# PCB-DISPLAYDOGM2.net
KiCad netlist of a schematic drawn in EAGLE
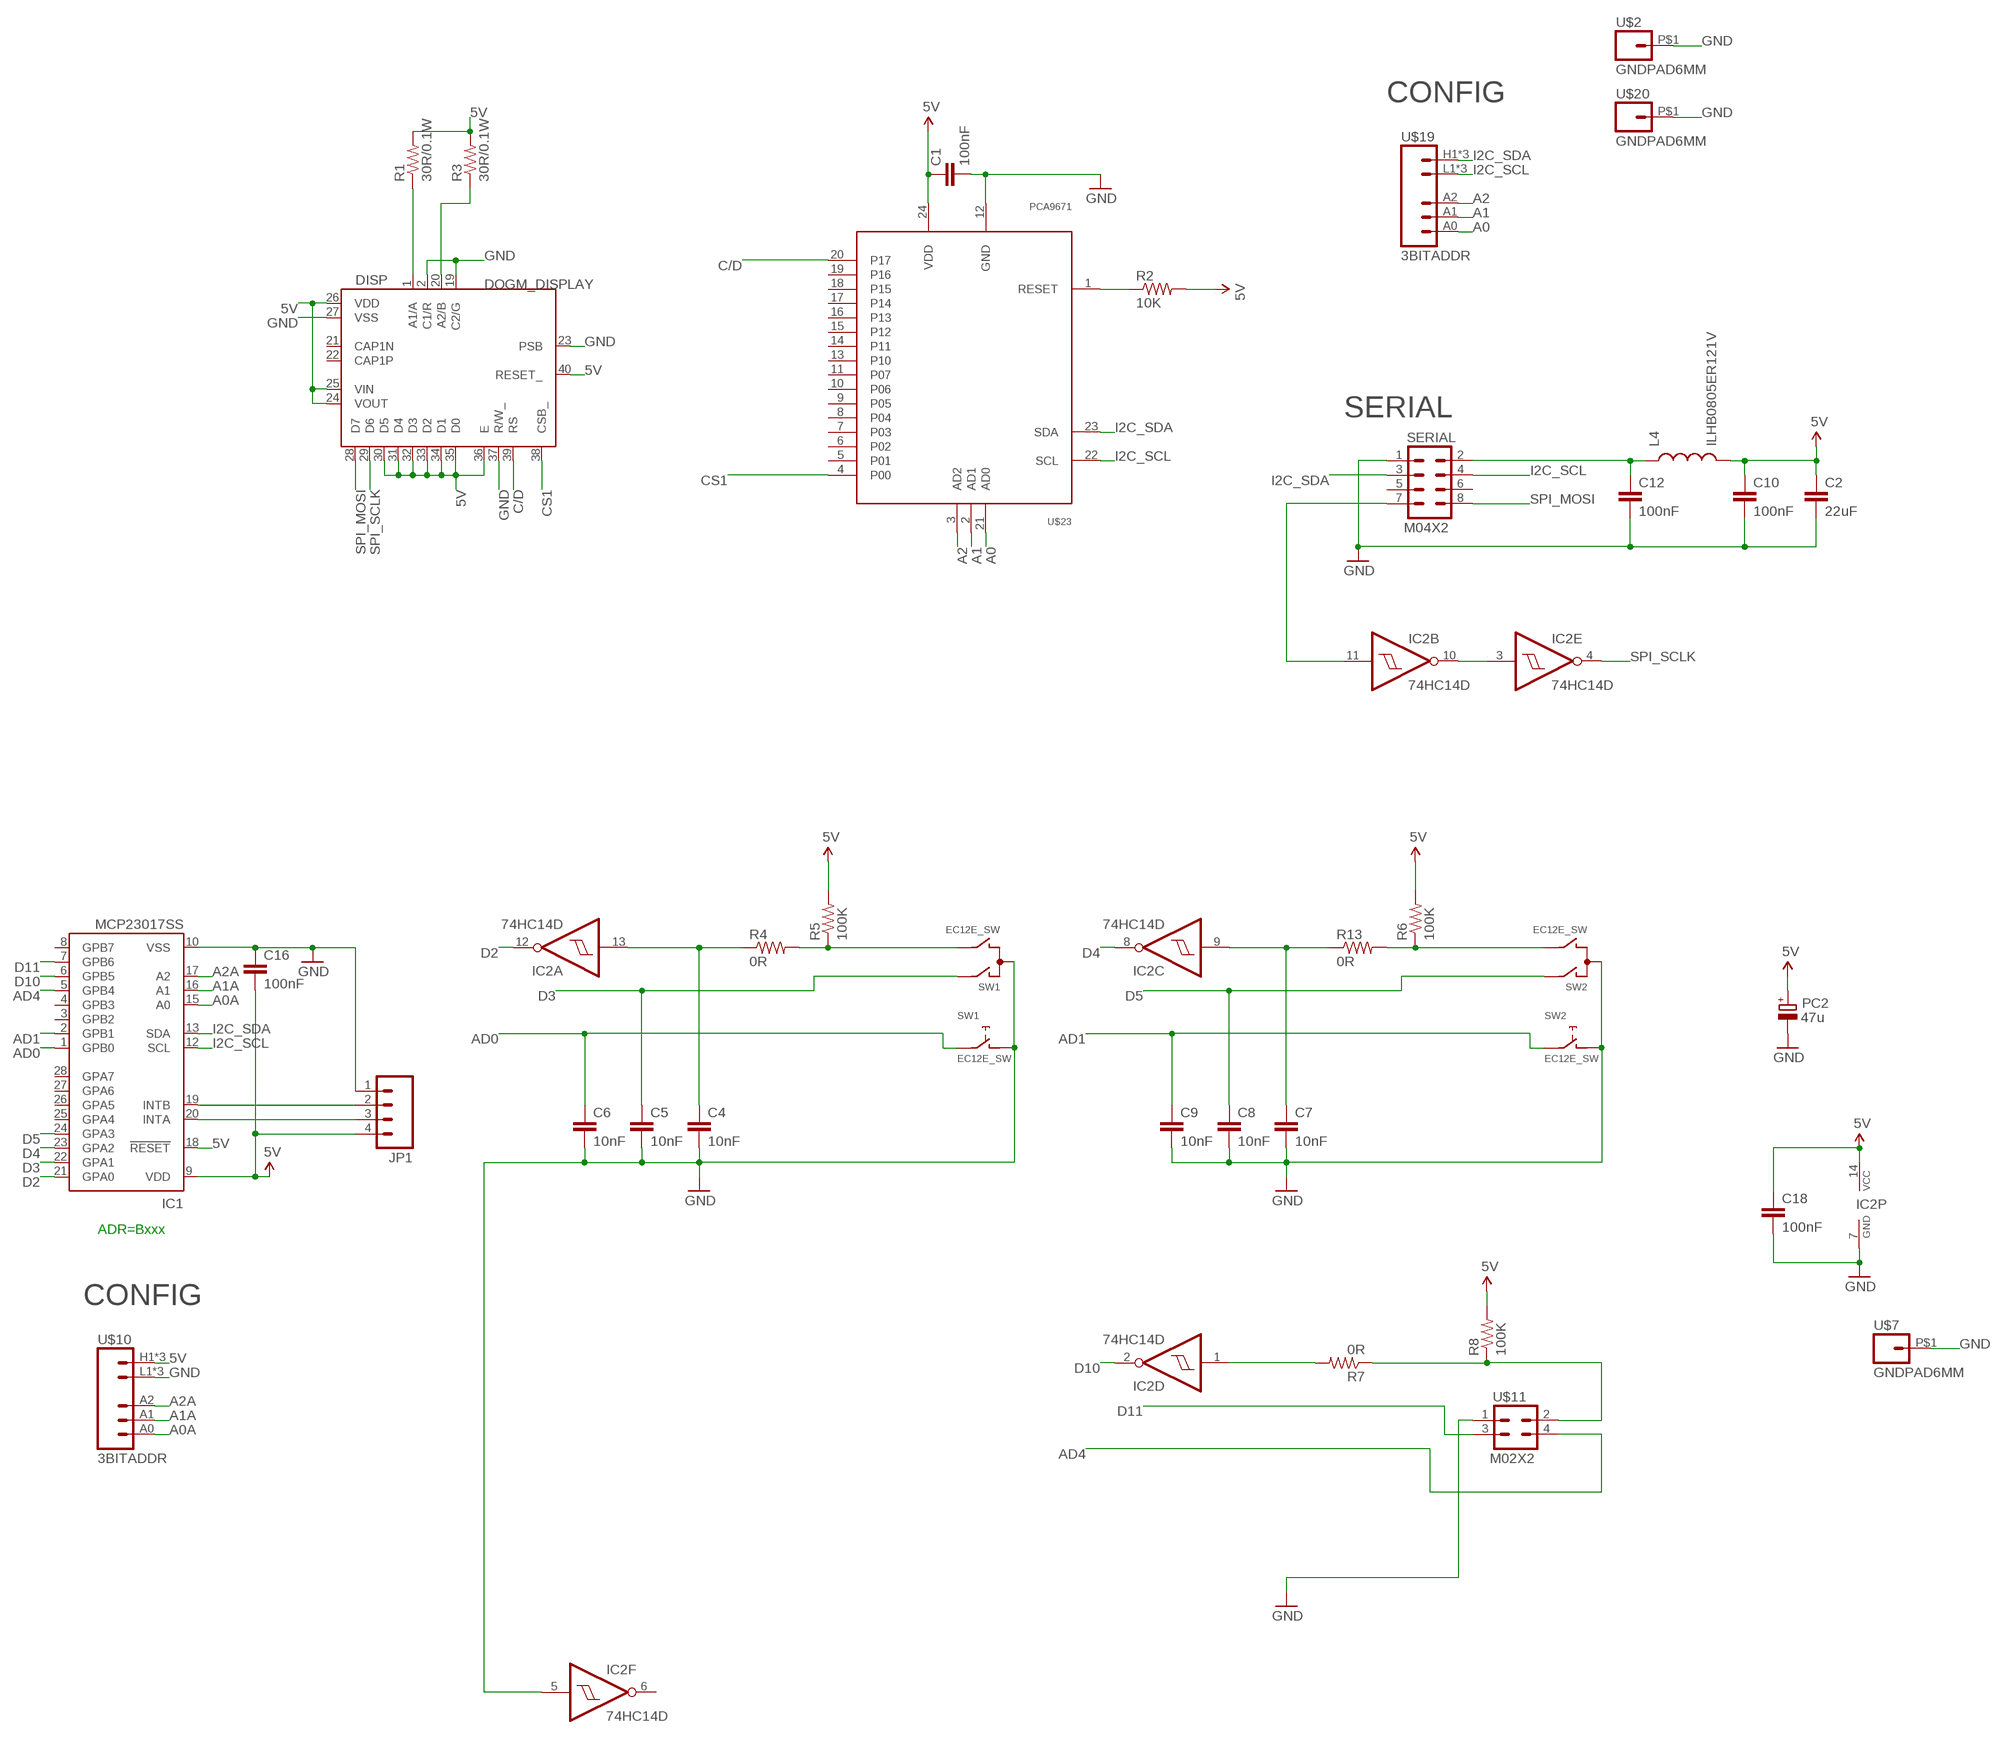
[diagram p0: schematic, sheet 1]

(export (version "E")
  (design (tool "Eeschema 10.0.6"))
  (components
    (comp (ref "C1")
      (value "100nF")
      (footprint "eagle-import:0603-CAP")
      (libsource (lib "eagle-import") (part "CAP0603-CAP"))
    )
    (comp (ref "C2")
      (value "22uF")
      (footprint "eagle-import:0805")
      (libsource (lib "eagle-import") (part "CAP0805"))
    )
    (comp (ref "C4")
      (value "10nF")
      (footprint "eagle-import:0603-CAP")
      (libsource (lib "eagle-import") (part "CAP0603-CAP"))
    )
    (comp (ref "C5")
      (value "10nF")
      (footprint "eagle-import:0603-CAP")
      (libsource (lib "eagle-import") (part "CAP0603-CAP"))
    )
    (comp (ref "C6")
      (value "10nF")
      (footprint "eagle-import:0603-CAP")
      (libsource (lib "eagle-import") (part "CAP0603-CAP"))
    )
    (comp (ref "C7")
      (value "10nF")
      (footprint "eagle-import:0603-CAP")
      (libsource (lib "eagle-import") (part "CAP0603-CAP"))
    )
    (comp (ref "C8")
      (value "10nF")
      (footprint "eagle-import:0603-CAP")
      (libsource (lib "eagle-import") (part "CAP0603-CAP"))
    )
    (comp (ref "C9")
      (value "10nF")
      (footprint "eagle-import:0603-CAP")
      (libsource (lib "eagle-import") (part "CAP0603-CAP"))
    )
    (comp (ref "C10")
      (value "100nF")
      (footprint "eagle-import:0603-CAP")
      (libsource (lib "eagle-import") (part "CAP0603-CAP"))
    )
    (comp (ref "C12")
      (value "100nF")
      (footprint "eagle-import:0603-CAP")
      (libsource (lib "eagle-import") (part "CAP0603-CAP"))
    )
    (comp (ref "C16")
      (value "100nF")
      (footprint "eagle-import:0603-CAP")
      (libsource (lib "eagle-import") (part "CAP0603-CAP"))
    )
    (comp (ref "C18")
      (value "100nF")
      (footprint "eagle-import:0603-CAP")
      (libsource (lib "eagle-import") (part "CAP0603-CAP"))
    )
    (comp (ref "DISP")
      (value "DOGM_DISPLAY")
      (footprint "eagle-import:DOGM")
      (libsource (lib "eagle-import") (part "DOGM_DISPLAY"))
    )
    (comp (ref "IC1")
      (value "MCP23017SS")
      (footprint "eagle-import:SSOP28")
      (fields
        (field (name "MF") "MICROCHIP")
        (field (name "MPN") "MCP23017-E/SS")
        (field (name "MPN_1") "MCP23017-E/SS")
        (field (name "OC_FARNELL") "1467674")
        (field (name "OC_NEWARK") "31K2960")
      )
      (libsource (lib "eagle-import") (part "MCP23017SS"))
    )
    (comp (ref "IC2")
      (value "74HC14D")
      (footprint "eagle-import:SO14")
      (libsource (lib "eagle-import") (part "7414DHC"))
    )
    (comp (ref "JP1")
      (value "M04PTH")
      (footprint "eagle-import:1X04")
      (libsource (lib "eagle-import") (part "M04PTH"))
    )
    (comp (ref "L4")
      (value "ILHB0805ER121V")
      (footprint "eagle-import:0805")
      (libsource (lib "eagle-import") (part "INDUCTOR0805"))
    )
    (comp (ref "PC2")
      (value "47u")
      (footprint "eagle-import:PANASONIC_D")
      (libsource (lib "eagle-import") (part "CPOL-EUD"))
    )
    (comp (ref "R1")
      (value "30R/0.1W")
      (footprint "eagle-import:0603-RES")
      (libsource (lib "eagle-import") (part "RESISTOR0603-RES"))
    )
    (comp (ref "R2")
      (value "10K")
      (footprint "eagle-import:0603-RES")
      (libsource (lib "eagle-import") (part "RESISTOR0603-RES"))
    )
    (comp (ref "R3")
      (value "30R/0.1W")
      (footprint "eagle-import:0603-RES")
      (libsource (lib "eagle-import") (part "RESISTOR0603-RES"))
    )
    (comp (ref "R4")
      (value "0R")
      (footprint "eagle-import:0603-RES")
      (libsource (lib "eagle-import") (part "RESISTOR0603-RES"))
    )
    (comp (ref "R5")
      (value "100K")
      (footprint "eagle-import:0603-RES")
      (libsource (lib "eagle-import") (part "RESISTOR0603-RES"))
    )
    (comp (ref "R6")
      (value "100K")
      (footprint "eagle-import:0603-RES")
      (libsource (lib "eagle-import") (part "RESISTOR0603-RES"))
    )
    (comp (ref "R7")
      (value "0R")
      (footprint "eagle-import:0603-RES")
      (libsource (lib "eagle-import") (part "RESISTOR0603-RES"))
    )
    (comp (ref "R8")
      (value "100K")
      (footprint "eagle-import:0603-RES")
      (libsource (lib "eagle-import") (part "RESISTOR0603-RES"))
    )
    (comp (ref "R13")
      (value "0R")
      (footprint "eagle-import:0603-RES")
      (libsource (lib "eagle-import") (part "RESISTOR0603-RES"))
    )
    (comp (ref "SERIAL")
      (value "M04X2")
      (footprint "eagle-import:2X4")
      (libsource (lib "eagle-import") (part "M04X2"))
    )
    (comp (ref "SW1")
      (value "EC12E_SW")
      (footprint "eagle-import:ALPS_EC12E_SW")
      (fields (field (name "MPN") "EC12E2424407"))
      (libsource (lib "eagle-import") (part "EC12E_SW"))
    )
    (comp (ref "SW2")
      (value "EC12E_SW")
      (footprint "eagle-import:ALPS_EC12E_SW")
      (fields (field (name "MPN") "EC12E2424407"))
      (libsource (lib "eagle-import") (part "EC12E_SW"))
    )
    (comp (ref "U$2")
      (value "GNDPAD6MM")
      (footprint "eagle-import:3.2MMPAD6MM")
      (libsource (lib "eagle-import") (part "GNDPAD6MM"))
    )
    (comp (ref "U$7")
      (value "GNDPAD6MM")
      (footprint "eagle-import:3.2MMPAD6MM")
      (libsource (lib "eagle-import") (part "GNDPAD6MM"))
    )
    (comp (ref "U$10")
      (value "3BITADDR")
      (footprint "eagle-import:3BITADDR")
      (libsource (lib "eagle-import") (part "3BITADDR"))
    )
    (comp (ref "U$11")
      (value "M02X2")
      (footprint "eagle-import:2X2")
      (libsource (lib "eagle-import") (part "M02X2"))
    )
    (comp (ref "U$19")
      (value "3BITADDR")
      (footprint "eagle-import:3BITADDR")
      (libsource (lib "eagle-import") (part "3BITADDR"))
    )
    (comp (ref "U$20")
      (value "GNDPAD6MM")
      (footprint "eagle-import:3.2MMPAD6MM")
      (libsource (lib "eagle-import") (part "GNDPAD6MM"))
    )
    (comp (ref "U$23")
      (value "PCA9671")
      (footprint "eagle-import:TSSOP24")
      (libsource (lib "eagle-import") (part "PCA9671"))
    )
  )
  (nets
    (net (code "1") (name "5V") (class "Default")
      (node (ref "C1") (pin "1") (pinfunction "1_1") (pintype "passive"))
      (node (ref "C10") (pin "1") (pinfunction "1_1") (pintype "passive"))
      (node (ref "C16") (pin "2") (pinfunction "2_2") (pintype "passive"))
      (node (ref "C18") (pin "1") (pinfunction "1_1") (pintype "passive"))
      (node (ref "C2") (pin "1") (pinfunction "1_1") (pintype "passive"))
      (node (ref "DISP") (pin "24") (pinfunction "VOUT_24") (pintype "bidirectional"))
      (node (ref "DISP") (pin "25") (pinfunction "VIN_25") (pintype "bidirectional"))
      (node (ref "DISP") (pin "26") (pinfunction "VDD_26") (pintype "power_in"))
      (node (ref "DISP") (pin "30") (pinfunction "D5_30") (pintype "bidirectional"))
      (node (ref "DISP") (pin "31") (pinfunction "D4_31") (pintype "bidirectional"))
      (node (ref "DISP") (pin "32") (pinfunction "D3_32") (pintype "bidirectional"))
      (node (ref "DISP") (pin "33") (pinfunction "D2_33") (pintype "bidirectional"))
      (node (ref "DISP") (pin "34") (pinfunction "D1_34") (pintype "bidirectional"))
      (node (ref "DISP") (pin "35") (pinfunction "D0_35") (pintype "bidirectional"))
      (node (ref "DISP") (pin "36") (pinfunction "E_36") (pintype "bidirectional"))
      (node (ref "DISP") (pin "40") (pinfunction "RESET__40") (pintype "bidirectional"))
      (node (ref "IC1") (pin "18") (pinfunction "~{RESET}_18") (pintype "input"))
      (node (ref "IC1") (pin "9") (pinfunction "VDD_9") (pintype "power_in"))
      (node (ref "IC2") (pin "14") (pinfunction "VCC_14") (pintype "power_in"))
      (node (ref "JP1") (pin "4") (pinfunction "4_4") (pintype "passive"))
      (node (ref "L4") (pin "2") (pinfunction "2_2") (pintype "passive"))
      (node (ref "PC2") (pin "+") (pinfunction "+_+") (pintype "passive"))
      (node (ref "R1") (pin "2") (pinfunction "2_2") (pintype "passive"))
      (node (ref "R2") (pin "2") (pinfunction "2_2") (pintype "passive"))
      (node (ref "R3") (pin "2") (pinfunction "2_2") (pintype "passive"))
      (node (ref "R5") (pin "2") (pinfunction "2_2") (pintype "passive"))
      (node (ref "R6") (pin "2") (pinfunction "2_2") (pintype "passive"))
      (node (ref "R8") (pin "2") (pinfunction "2_2") (pintype "passive"))
      (node (ref "U$10") (pin "H1") (pinfunction "VCC_H1") (pintype "passive"))
      (node (ref "U$10") (pin "H2") (pinfunction "VCC_H2") (pintype "passive"))
      (node (ref "U$10") (pin "H3") (pinfunction "VCC_H3") (pintype "passive"))
      (node (ref "U$23") (pin "24") (pinfunction "VDD_24") (pintype "power_in"))
    )
    (net (code "2") (name "A0") (class "Default")
      (node (ref "U$19") (pin "A0") (pinfunction "A0_A0") (pintype "passive"))
      (node (ref "U$23") (pin "21") (pinfunction "AD0_21") (pintype "input"))
    )
    (net (code "3") (name "A0A") (class "Default")
      (node (ref "IC1") (pin "15") (pinfunction "A0_15") (pintype "input"))
      (node (ref "U$10") (pin "A0") (pinfunction "A0_A0") (pintype "passive"))
    )
    (net (code "4") (name "A1") (class "Default")
      (node (ref "U$19") (pin "A1") (pinfunction "A1_A1") (pintype "passive"))
      (node (ref "U$23") (pin "2") (pinfunction "AD1_2") (pintype "input"))
    )
    (net (code "5") (name "A1A") (class "Default")
      (node (ref "IC1") (pin "16") (pinfunction "A1_16") (pintype "input"))
      (node (ref "U$10") (pin "A1") (pinfunction "A1_A1") (pintype "passive"))
    )
    (net (code "6") (name "A2") (class "Default")
      (node (ref "U$19") (pin "A2") (pinfunction "A2_A2") (pintype "passive"))
      (node (ref "U$23") (pin "3") (pinfunction "AD2_3") (pintype "input"))
    )
    (net (code "7") (name "A2A") (class "Default")
      (node (ref "IC1") (pin "17") (pinfunction "A2_17") (pintype "input"))
      (node (ref "U$10") (pin "A2") (pinfunction "A2_A2") (pintype "passive"))
    )
    (net (code "8") (name "AD0") (class "Default")
      (node (ref "C6") (pin "1") (pinfunction "1_1") (pintype "passive"))
      (node (ref "IC1") (pin "1") (pinfunction "GPB0_1") (pintype "bidirectional"))
      (node (ref "SW1") (pin "E") (pinfunction "2_E") (pintype "passive"))
    )
    (net (code "9") (name "AD1") (class "Default")
      (node (ref "C9") (pin "1") (pinfunction "1_1") (pintype "passive"))
      (node (ref "IC1") (pin "2") (pinfunction "GPB1_2") (pintype "bidirectional"))
      (node (ref "SW2") (pin "E") (pinfunction "2_E") (pintype "passive"))
    )
    (net (code "10") (name "AD4") (class "Default")
      (node (ref "IC1") (pin "5") (pinfunction "GPB4_5") (pintype "bidirectional"))
      (node (ref "U$11") (pin "4") (pinfunction "4_4") (pintype "passive"))
    )
    (net (code "11") (name "CS1") (class "Default")
      (node (ref "DISP") (pin "38") (pinfunction "CSB__38") (pintype "bidirectional"))
      (node (ref "U$23") (pin "4") (pinfunction "P00_4") (pintype "output"))
    )
    (net (code "12") (name "C{slash}D") (class "Default")
      (node (ref "DISP") (pin "39") (pinfunction "RS_39") (pintype "bidirectional"))
      (node (ref "U$23") (pin "20") (pinfunction "P17_20") (pintype "output"))
    )
    (net (code "13") (name "D2") (class "Default")
      (node (ref "IC1") (pin "21") (pinfunction "GPA0_21") (pintype "bidirectional"))
      (node (ref "IC2") (pin "12") (pinfunction "O_12") (pintype "output"))
    )
    (net (code "14") (name "D3") (class "Default")
      (node (ref "C5") (pin "1") (pinfunction "1_1") (pintype "passive"))
      (node (ref "IC1") (pin "22") (pinfunction "GPA1_22") (pintype "bidirectional"))
      (node (ref "SW1") (pin "A") (pinfunction "A_A") (pintype "passive"))
    )
    (net (code "15") (name "D4") (class "Default")
      (node (ref "IC1") (pin "23") (pinfunction "GPA2_23") (pintype "bidirectional"))
      (node (ref "IC2") (pin "8") (pinfunction "O_8") (pintype "output"))
    )
    (net (code "16") (name "D5") (class "Default")
      (node (ref "C8") (pin "1") (pinfunction "1_1") (pintype "passive"))
      (node (ref "IC1") (pin "24") (pinfunction "GPA3_24") (pintype "bidirectional"))
      (node (ref "SW2") (pin "A") (pinfunction "A_A") (pintype "passive"))
    )
    (net (code "17") (name "D10") (class "Default")
      (node (ref "IC1") (pin "6") (pinfunction "GPB5_6") (pintype "bidirectional"))
      (node (ref "IC2") (pin "2") (pinfunction "O_2") (pintype "output"))
    )
    (net (code "18") (name "D11") (class "Default")
      (node (ref "IC1") (pin "7") (pinfunction "GPB6_7") (pintype "bidirectional"))
      (node (ref "U$11") (pin "3") (pinfunction "3_3") (pintype "passive"))
    )
    (net (code "19") (name "GND") (class "Default")
      (node (ref "C1") (pin "2") (pinfunction "2_2") (pintype "passive"))
      (node (ref "C10") (pin "2") (pinfunction "2_2") (pintype "passive"))
      (node (ref "C12") (pin "2") (pinfunction "2_2") (pintype "passive"))
      (node (ref "C16") (pin "1") (pinfunction "1_1") (pintype "passive"))
      (node (ref "C18") (pin "2") (pinfunction "2_2") (pintype "passive"))
      (node (ref "C2") (pin "2") (pinfunction "2_2") (pintype "passive"))
      (node (ref "C4") (pin "2") (pinfunction "2_2") (pintype "passive"))
      (node (ref "C5") (pin "2") (pinfunction "2_2") (pintype "passive"))
      (node (ref "C6") (pin "2") (pinfunction "2_2") (pintype "passive"))
      (node (ref "C7") (pin "2") (pinfunction "2_2") (pintype "passive"))
      (node (ref "C8") (pin "2") (pinfunction "2_2") (pintype "passive"))
      (node (ref "C9") (pin "2") (pinfunction "2_2") (pintype "passive"))
      (node (ref "DISP") (pin "19") (pinfunction "C2/G_19") (pintype "bidirectional"))
      (node (ref "DISP") (pin "2") (pinfunction "C1/R_2") (pintype "bidirectional"))
      (node (ref "DISP") (pin "23") (pinfunction "PSB_23") (pintype "bidirectional"))
      (node (ref "DISP") (pin "27") (pinfunction "VSS_27") (pintype "power_in"))
      (node (ref "DISP") (pin "37") (pinfunction "R/W__37") (pintype "bidirectional"))
      (node (ref "IC1") (pin "10") (pinfunction "VSS_10") (pintype "power_in"))
      (node (ref "IC2") (pin "5") (pinfunction "I_5") (pintype "input"))
      (node (ref "IC2") (pin "7") (pinfunction "GND_7") (pintype "power_in"))
      (node (ref "JP1") (pin "1") (pinfunction "1_1") (pintype "passive"))
      (node (ref "PC2") (pin "-") (pinfunction "-_-") (pintype "passive"))
      (node (ref "SERIAL") (pin "1") (pinfunction "1_1") (pintype "passive"))
      (node (ref "SW1") (pin "C") (pinfunction "C_C") (pintype "passive"))
      (node (ref "SW1") (pin "D") (pinfunction "1_D") (pintype "passive"))
      (node (ref "SW2") (pin "C") (pinfunction "C_C") (pintype "passive"))
      (node (ref "SW2") (pin "D") (pinfunction "1_D") (pintype "passive"))
      (node (ref "U$10") (pin "L1") (pinfunction "GND_L1") (pintype "passive"))
      (node (ref "U$10") (pin "L2") (pinfunction "GND_L2") (pintype "passive"))
      (node (ref "U$10") (pin "L3") (pinfunction "GND_L3") (pintype "passive"))
      (node (ref "U$11") (pin "1") (pinfunction "1_1") (pintype "passive"))
      (node (ref "U$2") (pin "P$1") (pinfunction "1_P$1") (pintype "passive"))
      (node (ref "U$20") (pin "P$1") (pinfunction "1_P$1") (pintype "passive"))
      (node (ref "U$23") (pin "12") (pinfunction "GND_12") (pintype "power_in"))
      (node (ref "U$7") (pin "P$1") (pinfunction "1_P$1") (pintype "passive"))
    )
    (net (code "20") (name "I2C_SCL") (class "Default")
      (node (ref "IC1") (pin "12") (pinfunction "SCL_12") (pintype "input"))
      (node (ref "SERIAL") (pin "4") (pinfunction "4_4") (pintype "passive"))
      (node (ref "U$19") (pin "L1") (pinfunction "GND_L1") (pintype "passive"))
      (node (ref "U$19") (pin "L2") (pinfunction "GND_L2") (pintype "passive"))
      (node (ref "U$19") (pin "L3") (pinfunction "GND_L3") (pintype "passive"))
      (node (ref "U$23") (pin "22") (pinfunction "SCL_22") (pintype "input"))
    )
    (net (code "21") (name "I2C_SDA") (class "Default")
      (node (ref "IC1") (pin "13") (pinfunction "SDA_13") (pintype "bidirectional"))
      (node (ref "SERIAL") (pin "3") (pinfunction "3_3") (pintype "passive"))
      (node (ref "U$19") (pin "H1") (pinfunction "VCC_H1") (pintype "passive"))
      (node (ref "U$19") (pin "H2") (pinfunction "VCC_H2") (pintype "passive"))
      (node (ref "U$19") (pin "H3") (pinfunction "VCC_H3") (pintype "passive"))
      (node (ref "U$23") (pin "23") (pinfunction "SDA_23") (pintype "input"))
    )
    (net (code "22") (name "Net-(C12-Pad1)") (class "Default")
      (node (ref "C12") (pin "1") (pinfunction "1_1") (pintype "passive"))
      (node (ref "L4") (pin "1") (pinfunction "1_1") (pintype "passive"))
      (node (ref "SERIAL") (pin "2") (pinfunction "2_2") (pintype "passive"))
    )
    (net (code "23") (name "Net-(DISP-A1{slash}A)") (class "Default")
      (node (ref "DISP") (pin "1") (pinfunction "A1/A_1") (pintype "bidirectional"))
      (node (ref "R1") (pin "1") (pinfunction "1_1") (pintype "passive"))
    )
    (net (code "24") (name "Net-(DISP-A2{slash}B)") (class "Default")
      (node (ref "DISP") (pin "20") (pinfunction "A2/B_20") (pintype "bidirectional"))
      (node (ref "R3") (pin "1") (pinfunction "1_1") (pintype "passive"))
    )
    (net (code "25") (name "Net-(IC1-INTA)") (class "Default")
      (node (ref "IC1") (pin "20") (pinfunction "INTA_20") (pintype "output"))
      (node (ref "JP1") (pin "3") (pinfunction "3_3") (pintype "passive"))
    )
    (net (code "26") (name "Net-(IC1-INTB)") (class "Default")
      (node (ref "IC1") (pin "19") (pinfunction "INTB_19") (pintype "output"))
      (node (ref "JP1") (pin "2") (pinfunction "2_2") (pintype "passive"))
    )
    (net (code "27") (name "Net-(IC2A-I)") (class "Default")
      (node (ref "C4") (pin "1") (pinfunction "1_1") (pintype "passive"))
      (node (ref "IC2") (pin "13") (pinfunction "I_13") (pintype "input"))
      (node (ref "R4") (pin "1") (pinfunction "1_1") (pintype "passive"))
    )
    (net (code "28") (name "Net-(IC2B-I)") (class "Default")
      (node (ref "IC2") (pin "11") (pinfunction "I_11") (pintype "input"))
      (node (ref "SERIAL") (pin "7") (pinfunction "7_7") (pintype "passive"))
    )
    (net (code "29") (name "Net-(IC2B-O)") (class "Default")
      (node (ref "IC2") (pin "10") (pinfunction "O_10") (pintype "output"))
      (node (ref "IC2") (pin "3") (pinfunction "I_3") (pintype "input"))
    )
    (net (code "30") (name "Net-(IC2C-I)") (class "Default")
      (node (ref "C7") (pin "1") (pinfunction "1_1") (pintype "passive"))
      (node (ref "IC2") (pin "9") (pinfunction "I_9") (pintype "input"))
      (node (ref "R13") (pin "1") (pinfunction "1_1") (pintype "passive"))
    )
    (net (code "31") (name "Net-(IC2D-I)") (class "Default")
      (node (ref "IC2") (pin "1") (pinfunction "I_1") (pintype "input"))
      (node (ref "R7") (pin "2") (pinfunction "2_2") (pintype "passive"))
    )
    (net (code "32") (name "Net-(R4-Pad2)") (class "Default")
      (node (ref "R4") (pin "2") (pinfunction "2_2") (pintype "passive"))
      (node (ref "R5") (pin "1") (pinfunction "1_1") (pintype "passive"))
      (node (ref "SW1") (pin "B") (pinfunction "B_B") (pintype "passive"))
    )
    (net (code "33") (name "Net-(R7-Pad1)") (class "Default")
      (node (ref "R7") (pin "1") (pinfunction "1_1") (pintype "passive"))
      (node (ref "R8") (pin "1") (pinfunction "1_1") (pintype "passive"))
      (node (ref "U$11") (pin "2") (pinfunction "2_2") (pintype "passive"))
    )
    (net (code "34") (name "Net-(R13-Pad2)") (class "Default")
      (node (ref "R13") (pin "2") (pinfunction "2_2") (pintype "passive"))
      (node (ref "R6") (pin "1") (pinfunction "1_1") (pintype "passive"))
      (node (ref "SW2") (pin "B") (pinfunction "B_B") (pintype "passive"))
    )
    (net (code "35") (name "Net-(U$23-RESET)") (class "Default")
      (node (ref "R2") (pin "1") (pinfunction "1_1") (pintype "passive"))
      (node (ref "U$23") (pin "1") (pinfunction "RESET_1") (pintype "input"))
    )
    (net (code "36") (name "SPI_MOSI") (class "Default")
      (node (ref "DISP") (pin "28") (pinfunction "D7_28") (pintype "bidirectional"))
      (node (ref "SERIAL") (pin "8") (pinfunction "8_8") (pintype "passive"))
    )
    (net (code "37") (name "SPI_SCLK") (class "Default")
      (node (ref "DISP") (pin "29") (pinfunction "D6_29") (pintype "bidirectional"))
      (node (ref "IC2") (pin "4") (pinfunction "O_4") (pintype "output"))
    )
    (net (code "38") (name "unconnected-(DISP-CAP1N-Pad21)") (class "Default")
      (node (ref "DISP") (pin "21") (pinfunction "CAP1N_21") (pintype "bidirectional"))
    )
    (net (code "39") (name "unconnected-(DISP-CAP1P-Pad22)") (class "Default")
      (node (ref "DISP") (pin "22") (pinfunction "CAP1P_22") (pintype "bidirectional"))
    )
    (net (code "40") (name "unconnected-(IC1-GPA4-Pad25)") (class "Default")
      (node (ref "IC1") (pin "25") (pinfunction "GPA4_25") (pintype "bidirectional"))
    )
    (net (code "41") (name "unconnected-(IC1-GPA5-Pad26)") (class "Default")
      (node (ref "IC1") (pin "26") (pinfunction "GPA5_26") (pintype "bidirectional"))
    )
    (net (code "42") (name "unconnected-(IC1-GPA6-Pad27)") (class "Default")
      (node (ref "IC1") (pin "27") (pinfunction "GPA6_27") (pintype "bidirectional"))
    )
    (net (code "43") (name "unconnected-(IC1-GPA7-Pad28)") (class "Default")
      (node (ref "IC1") (pin "28") (pinfunction "GPA7_28") (pintype "bidirectional"))
    )
    (net (code "44") (name "unconnected-(IC1-GPB2-Pad3)") (class "Default")
      (node (ref "IC1") (pin "3") (pinfunction "GPB2_3") (pintype "bidirectional"))
    )
    (net (code "45") (name "unconnected-(IC1-GPB3-Pad4)") (class "Default")
      (node (ref "IC1") (pin "4") (pinfunction "GPB3_4") (pintype "bidirectional"))
    )
    (net (code "46") (name "unconnected-(IC1-GPB7-Pad8)") (class "Default")
      (node (ref "IC1") (pin "8") (pinfunction "GPB7_8") (pintype "bidirectional"))
    )
    (net (code "47") (name "unconnected-(IC2F-O-Pad6)") (class "Default")
      (node (ref "IC2") (pin "6") (pinfunction "O_6") (pintype "output"))
    )
    (net (code "48") (name "unconnected-(SERIAL-Pad5)") (class "Default")
      (node (ref "SERIAL") (pin "5") (pinfunction "5_5") (pintype "passive"))
    )
    (net (code "49") (name "unconnected-(SERIAL-Pad6)") (class "Default")
      (node (ref "SERIAL") (pin "6") (pinfunction "6_6") (pintype "passive"))
    )
    (net (code "50") (name "unconnected-(U$23-P01-Pad5)") (class "Default")
      (node (ref "U$23") (pin "5") (pinfunction "P01_5") (pintype "output"))
    )
    (net (code "51") (name "unconnected-(U$23-P02-Pad6)") (class "Default")
      (node (ref "U$23") (pin "6") (pinfunction "P02_6") (pintype "output"))
    )
    (net (code "52") (name "unconnected-(U$23-P03-Pad7)") (class "Default")
      (node (ref "U$23") (pin "7") (pinfunction "P03_7") (pintype "output"))
    )
    (net (code "53") (name "unconnected-(U$23-P04-Pad8)") (class "Default")
      (node (ref "U$23") (pin "8") (pinfunction "P04_8") (pintype "output"))
    )
    (net (code "54") (name "unconnected-(U$23-P05-Pad9)") (class "Default")
      (node (ref "U$23") (pin "9") (pinfunction "P05_9") (pintype "output"))
    )
    (net (code "55") (name "unconnected-(U$23-P06-Pad10)") (class "Default")
      (node (ref "U$23") (pin "10") (pinfunction "P06_10") (pintype "output"))
    )
    (net (code "56") (name "unconnected-(U$23-P07-Pad11)") (class "Default")
      (node (ref "U$23") (pin "11") (pinfunction "P07_11") (pintype "output"))
    )
    (net (code "57") (name "unconnected-(U$23-P10-Pad13)") (class "Default")
      (node (ref "U$23") (pin "13") (pinfunction "P10_13") (pintype "output"))
    )
    (net (code "58") (name "unconnected-(U$23-P11-Pad14)") (class "Default")
      (node (ref "U$23") (pin "14") (pinfunction "P11_14") (pintype "output"))
    )
    (net (code "59") (name "unconnected-(U$23-P12-Pad15)") (class "Default")
      (node (ref "U$23") (pin "15") (pinfunction "P12_15") (pintype "output"))
    )
    (net (code "60") (name "unconnected-(U$23-P13-Pad16)") (class "Default")
      (node (ref "U$23") (pin "16") (pinfunction "P13_16") (pintype "output"))
    )
    (net (code "61") (name "unconnected-(U$23-P14-Pad17)") (class "Default")
      (node (ref "U$23") (pin "17") (pinfunction "P14_17") (pintype "output"))
    )
    (net (code "62") (name "unconnected-(U$23-P15-Pad18)") (class "Default")
      (node (ref "U$23") (pin "18") (pinfunction "P15_18") (pintype "output"))
    )
    (net (code "63") (name "unconnected-(U$23-P16-Pad19)") (class "Default")
      (node (ref "U$23") (pin "19") (pinfunction "P16_19") (pintype "output"))
    )
  )
)
